# cw312_template_cardedge.net
KiCad netlist of a schematic drawn in Altium Designer
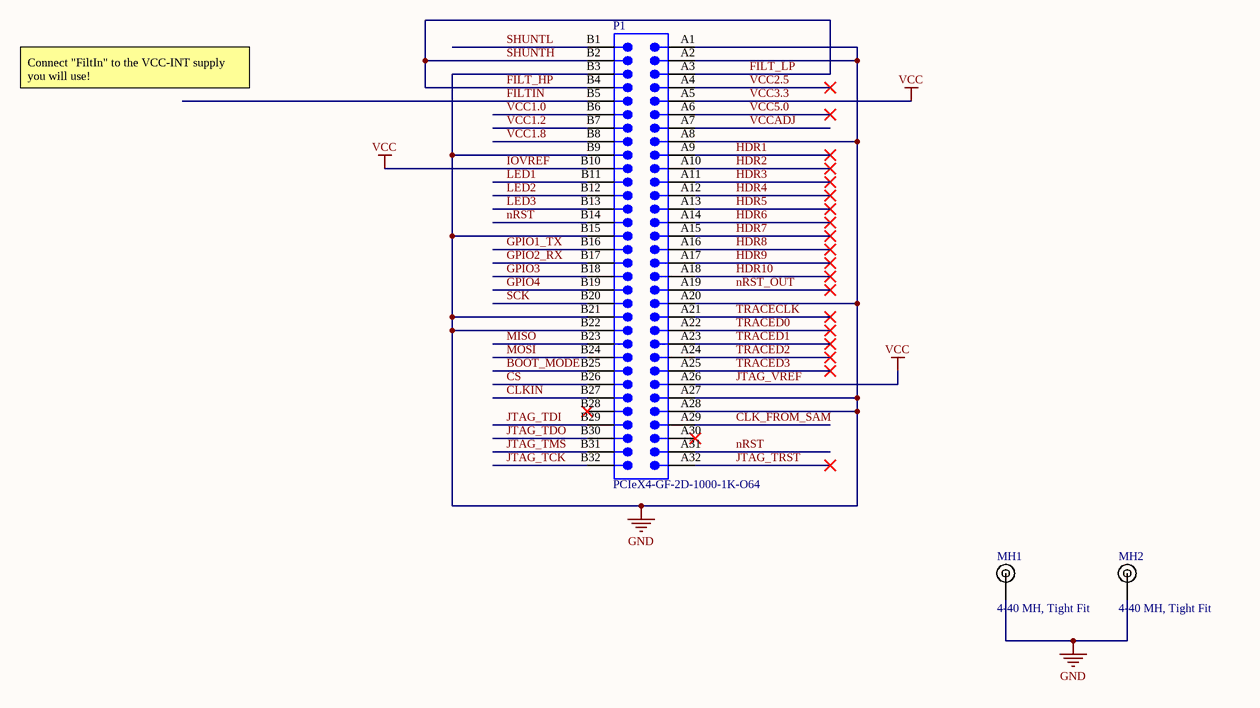
[diagram p0: cw312_template_cardedge.SchDoc]

(export (version "E")
  (design (tool "Eeschema 10.0.6"))
  (components
    (comp (ref "MH1")
      (value "4-40 MH, Tight Fit")
      (footprint "MOUNT_#4_TIGHT")
      (description "Machine screw 4-40 Mounting Hole")
      (fields (field (name "PART NUMBER") "MOUNT_#4_TIGHT"))
      (libsource (lib "NewAE_AltiumLib") (part "Mounting_Hole"))
    )
    (comp (ref "MH2")
      (value "4-40 MH, Tight Fit")
      (footprint "MOUNT_#4_TIGHT")
      (description "Machine screw 4-40 Mounting Hole")
      (fields (field (name "PART NUMBER") "MOUNT_#4_TIGHT"))
      (libsource (lib "NewAE_AltiumLib") (part "Mounting_Hole"))
    )
    (comp (ref "P1")
      (value "PCIeX4-GF-2D-1000-1K-O64")
      (footprint "PCIeX4-GF-2D-1000-1K-O64")
      (description "Golden finger, PCIeX4, Dual, Opposite, Pitch 1mm, 64-Position")
      (fields (field (name "PUBLISHER") "Altium"))
      (libsource (lib "Altium Content Vault") (part "PCIeX4-GF-2D-1000-1K-O64"))
    )
  )
  (nets
    (net (code "1") (name "/BOOT_MODE") (class "Default")
      (node (ref "P1") (pin "B25") (pinfunction "B25_B25") (pintype "passive"))
    )
    (net (code "2") (name "/CLKIN") (class "Default")
      (node (ref "P1") (pin "B27") (pinfunction "B27_B27") (pintype "passive"))
    )
    (net (code "3") (name "/CLK_FROM_SAM") (class "Default")
      (node (ref "P1") (pin "A29") (pinfunction "A29_A29") (pintype "passive"))
    )
    (net (code "4") (name "/CS") (class "Default")
      (node (ref "P1") (pin "B26") (pinfunction "B26_B26") (pintype "passive"))
    )
    (net (code "5") (name "/FILTIN") (class "Default")
      (node (ref "P1") (pin "B5") (pinfunction "B5_B5") (pintype "passive"))
    )
    (net (code "6") (name "/FILT_HP") (class "Default")
      (node (ref "P1") (pin "A3") (pinfunction "A3_A3") (pintype "passive"))
      (node (ref "P1") (pin "B2") (pinfunction "B2_B2") (pintype "passive"))
      (node (ref "P1") (pin "B4") (pinfunction "B4_B4") (pintype "passive"))
    )
    (net (code "7") (name "/GPIO1_TX") (class "Default")
      (node (ref "P1") (pin "B16") (pinfunction "B16_B16") (pintype "passive"))
    )
    (net (code "8") (name "/GPIO2_RX") (class "Default")
      (node (ref "P1") (pin "B17") (pinfunction "B17_B17") (pintype "passive"))
    )
    (net (code "9") (name "/GPIO3") (class "Default")
      (node (ref "P1") (pin "B18") (pinfunction "B18_B18") (pintype "passive"))
    )
    (net (code "10") (name "/GPIO4") (class "Default")
      (node (ref "P1") (pin "B19") (pinfunction "B19_B19") (pintype "passive"))
    )
    (net (code "11") (name "/HDR1") (class "Default")
      (node (ref "P1") (pin "A9") (pinfunction "A9_A9") (pintype "passive+no_connect"))
    )
    (net (code "12") (name "/HDR2") (class "Default")
      (node (ref "P1") (pin "A10") (pinfunction "A10_A10") (pintype "passive+no_connect"))
    )
    (net (code "13") (name "/HDR3") (class "Default")
      (node (ref "P1") (pin "A11") (pinfunction "A11_A11") (pintype "passive+no_connect"))
    )
    (net (code "14") (name "/HDR4") (class "Default")
      (node (ref "P1") (pin "A12") (pinfunction "A12_A12") (pintype "passive+no_connect"))
    )
    (net (code "15") (name "/HDR5") (class "Default")
      (node (ref "P1") (pin "A13") (pinfunction "A13_A13") (pintype "passive+no_connect"))
    )
    (net (code "16") (name "/HDR6") (class "Default")
      (node (ref "P1") (pin "A14") (pinfunction "A14_A14") (pintype "passive+no_connect"))
    )
    (net (code "17") (name "/HDR7") (class "Default")
      (node (ref "P1") (pin "A15") (pinfunction "A15_A15") (pintype "passive+no_connect"))
    )
    (net (code "18") (name "/HDR8") (class "Default")
      (node (ref "P1") (pin "A16") (pinfunction "A16_A16") (pintype "passive+no_connect"))
    )
    (net (code "19") (name "/HDR9") (class "Default")
      (node (ref "P1") (pin "A17") (pinfunction "A17_A17") (pintype "passive+no_connect"))
    )
    (net (code "20") (name "/HDR10") (class "Default")
      (node (ref "P1") (pin "A18") (pinfunction "A18_A18") (pintype "passive+no_connect"))
    )
    (net (code "21") (name "/JTAG_TCK") (class "Default")
      (node (ref "P1") (pin "B32") (pinfunction "B32_B32") (pintype "passive"))
    )
    (net (code "22") (name "/JTAG_TDI") (class "Default")
      (node (ref "P1") (pin "B29") (pinfunction "B29_B29") (pintype "passive"))
    )
    (net (code "23") (name "/JTAG_TDO") (class "Default")
      (node (ref "P1") (pin "B30") (pinfunction "B30_B30") (pintype "passive"))
    )
    (net (code "24") (name "/JTAG_TMS") (class "Default")
      (node (ref "P1") (pin "B31") (pinfunction "B31_B31") (pintype "passive"))
    )
    (net (code "25") (name "/JTAG_TRST") (class "Default")
      (node (ref "P1") (pin "A32") (pinfunction "A32_A32") (pintype "passive+no_connect"))
    )
    (net (code "26") (name "/LED1") (class "Default")
      (node (ref "P1") (pin "B11") (pinfunction "B11_B11") (pintype "passive"))
    )
    (net (code "27") (name "/LED2") (class "Default")
      (node (ref "P1") (pin "B12") (pinfunction "B12_B12") (pintype "passive"))
    )
    (net (code "28") (name "/LED3") (class "Default")
      (node (ref "P1") (pin "B13") (pinfunction "B13_B13") (pintype "passive"))
    )
    (net (code "29") (name "/MISO") (class "Default")
      (node (ref "P1") (pin "B23") (pinfunction "B23_B23") (pintype "passive"))
    )
    (net (code "30") (name "/MOSI") (class "Default")
      (node (ref "P1") (pin "B24") (pinfunction "B24_B24") (pintype "passive"))
    )
    (net (code "31") (name "/SCK") (class "Default")
      (node (ref "P1") (pin "B20") (pinfunction "B20_B20") (pintype "passive"))
    )
    (net (code "32") (name "/SHUNTL") (class "Default")
      (node (ref "P1") (pin "B1") (pinfunction "B1_B1") (pintype "passive"))
    )
    (net (code "33") (name "/TRACECLK") (class "Default")
      (node (ref "P1") (pin "A21") (pinfunction "A21_A21") (pintype "passive+no_connect"))
    )
    (net (code "34") (name "/TRACED0") (class "Default")
      (node (ref "P1") (pin "A22") (pinfunction "A22_A22") (pintype "passive+no_connect"))
    )
    (net (code "35") (name "/TRACED1") (class "Default")
      (node (ref "P1") (pin "A23") (pinfunction "A23_A23") (pintype "passive+no_connect"))
    )
    (net (code "36") (name "/TRACED2") (class "Default")
      (node (ref "P1") (pin "A24") (pinfunction "A24_A24") (pintype "passive+no_connect"))
    )
    (net (code "37") (name "/TRACED3") (class "Default")
      (node (ref "P1") (pin "A25") (pinfunction "A25_A25") (pintype "passive+no_connect"))
    )
    (net (code "38") (name "/VCC1.0") (class "Default")
      (node (ref "P1") (pin "B6") (pinfunction "B6_B6") (pintype "passive"))
    )
    (net (code "39") (name "/VCC1.2") (class "Default")
      (node (ref "P1") (pin "B7") (pinfunction "B7_B7") (pintype "passive"))
    )
    (net (code "40") (name "/VCC1.8") (class "Default")
      (node (ref "P1") (pin "B8") (pinfunction "B8_B8") (pintype "passive"))
    )
    (net (code "41") (name "/VCC2.5") (class "Default")
      (node (ref "P1") (pin "A4") (pinfunction "A4_A4") (pintype "passive+no_connect"))
    )
    (net (code "42") (name "/VCC5.0") (class "Default")
      (node (ref "P1") (pin "A6") (pinfunction "A6_A6") (pintype "passive+no_connect"))
    )
    (net (code "43") (name "/VCCADJ") (class "Default")
      (node (ref "P1") (pin "A7") (pinfunction "A7_A7") (pintype "passive"))
    )
    (net (code "44") (name "/nRST") (class "Default")
      (node (ref "P1") (pin "A31") (pinfunction "A31_A31") (pintype "passive"))
      (node (ref "P1") (pin "B14") (pinfunction "B14_B14") (pintype "passive"))
    )
    (net (code "45") (name "/nRST_OUT") (class "Default")
      (node (ref "P1") (pin "A19") (pinfunction "A19_A19") (pintype "passive+no_connect"))
    )
    (net (code "46") (name "GND") (class "Default")
      (node (ref "MH1") (pin "1") (pinfunction "1_1") (pintype "passive"))
      (node (ref "MH2") (pin "1") (pinfunction "1_1") (pintype "passive"))
      (node (ref "P1") (pin "A1") (pinfunction "A1_A1") (pintype "passive"))
      (node (ref "P1") (pin "A2") (pinfunction "A2_A2") (pintype "passive"))
      (node (ref "P1") (pin "A20") (pinfunction "A20_A20") (pintype "passive"))
      (node (ref "P1") (pin "A27") (pinfunction "A27_A27") (pintype "passive"))
      (node (ref "P1") (pin "A28") (pinfunction "A28_A28") (pintype "passive"))
      (node (ref "P1") (pin "A8") (pinfunction "A8_A8") (pintype "passive"))
      (node (ref "P1") (pin "B15") (pinfunction "B15_B15") (pintype "passive"))
      (node (ref "P1") (pin "B21") (pinfunction "B21_B21") (pintype "passive"))
      (node (ref "P1") (pin "B22") (pinfunction "B22_B22") (pintype "passive"))
      (node (ref "P1") (pin "B3") (pinfunction "B3_B3") (pintype "passive"))
      (node (ref "P1") (pin "B9") (pinfunction "B9_B9") (pintype "passive"))
    )
    (net (code "47") (name "VCC") (class "Default")
      (node (ref "P1") (pin "A26") (pinfunction "A26_A26") (pintype "passive"))
      (node (ref "P1") (pin "A5") (pinfunction "A5_A5") (pintype "passive"))
      (node (ref "P1") (pin "B10") (pinfunction "B10_B10") (pintype "passive"))
    )
    (net (code "48") (name "unconnected-(P1-PadA30)") (class "Default")
      (node (ref "P1") (pin "A30") (pinfunction "A30_A30") (pintype "passive+no_connect"))
    )
    (net (code "49") (name "unconnected-(P1-PadB28)") (class "Default")
      (node (ref "P1") (pin "B28") (pinfunction "B28_B28") (pintype "passive+no_connect"))
    )
  )
)
